# 1A20J4_1A21J8_A.net
KiCad netlist of a schematic drawn in Altium Designer
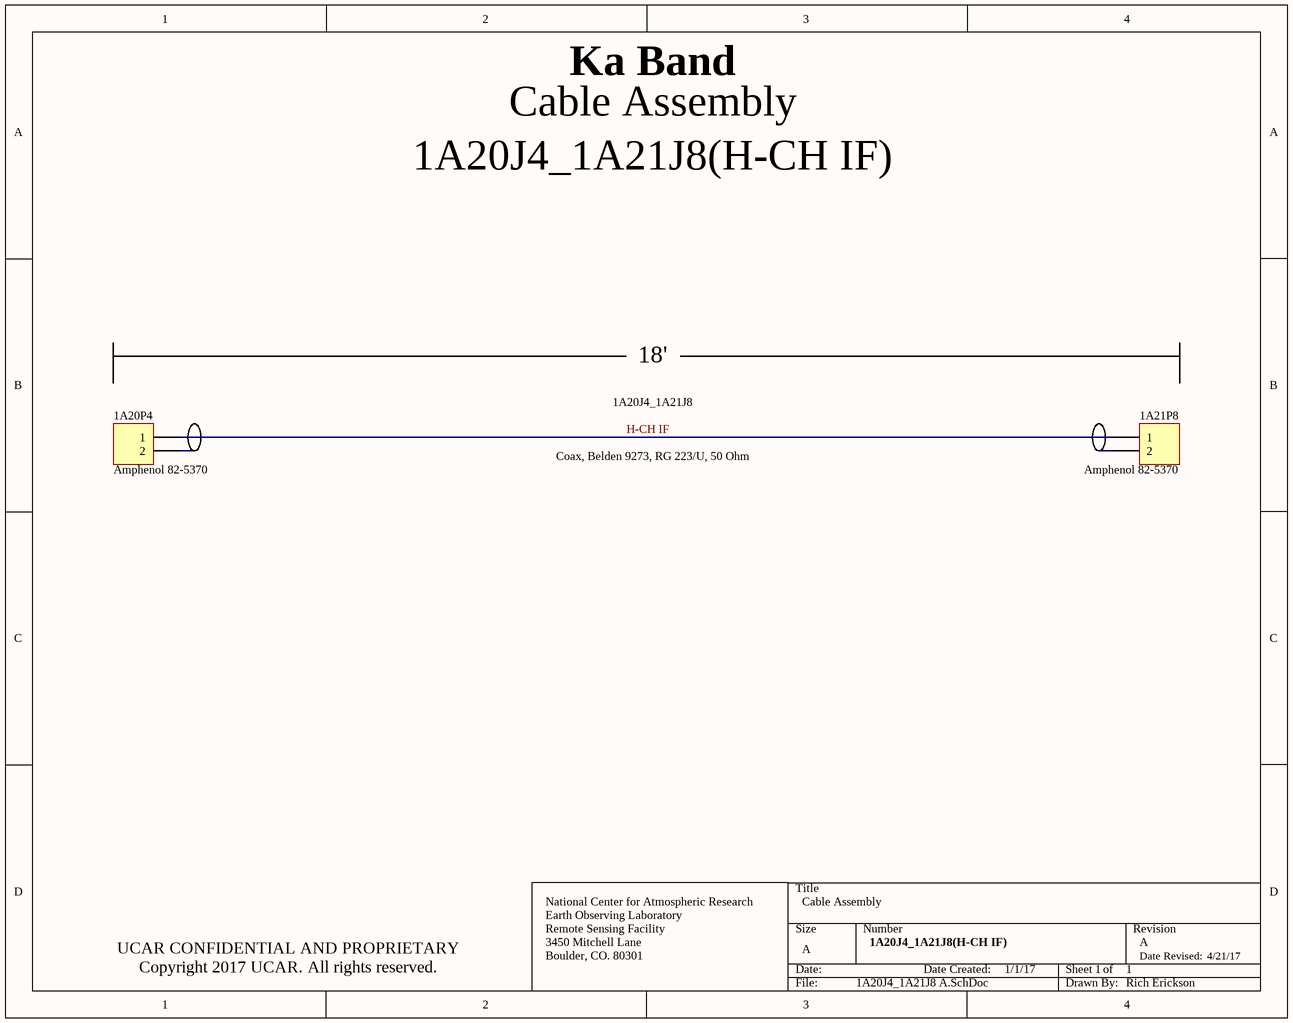
[diagram p0: 1A20J4_1A21J8 A.SchDoc]

(export (version "E")
  (design (tool "Eeschema 10.0.6"))
  (components
    (comp (ref "1A20P4")
      (value "Amphenol 82-5370")
      (footprint "HDR1X2")
      (description "Header, 2-Pin")
      (fields (field (name "PUBLISHER") "Altium Limited"))
      (libsource (lib "Miscellaneous Connectors") (part "Header 2"))
    )
    (comp (ref "1A21P8")
      (value "Amphenol 82-5370")
      (footprint "HDR1X2")
      (description "Header, 2-Pin")
      (fields (field (name "PUBLISHER") "Altium Limited"))
      (libsource (lib "") (part "Header 2_1"))
    )
  )
  (nets
    (net (code "1") (name "/H-CH IF") (class "Default")
      (node (ref "1A20P4") (pin "1") (pinfunction "1_1") (pintype "passive"))
      (node (ref "1A21P8") (pin "1") (pinfunction "1_1") (pintype "passive"))
    )
    (net (code "2") (name "unconnected-(1A20P4-Pad2)") (class "Default")
      (node (ref "1A20P4") (pin "2") (pinfunction "2_2") (pintype "passive"))
    )
    (net (code "3") (name "unconnected-(1A21P8-Pad2)") (class "Default")
      (node (ref "1A21P8") (pin "2") (pinfunction "2_2") (pintype "passive"))
    )
  )
)
